# Supply_GEM.net
KiCad netlist of a schematic drawn in Altium Designer
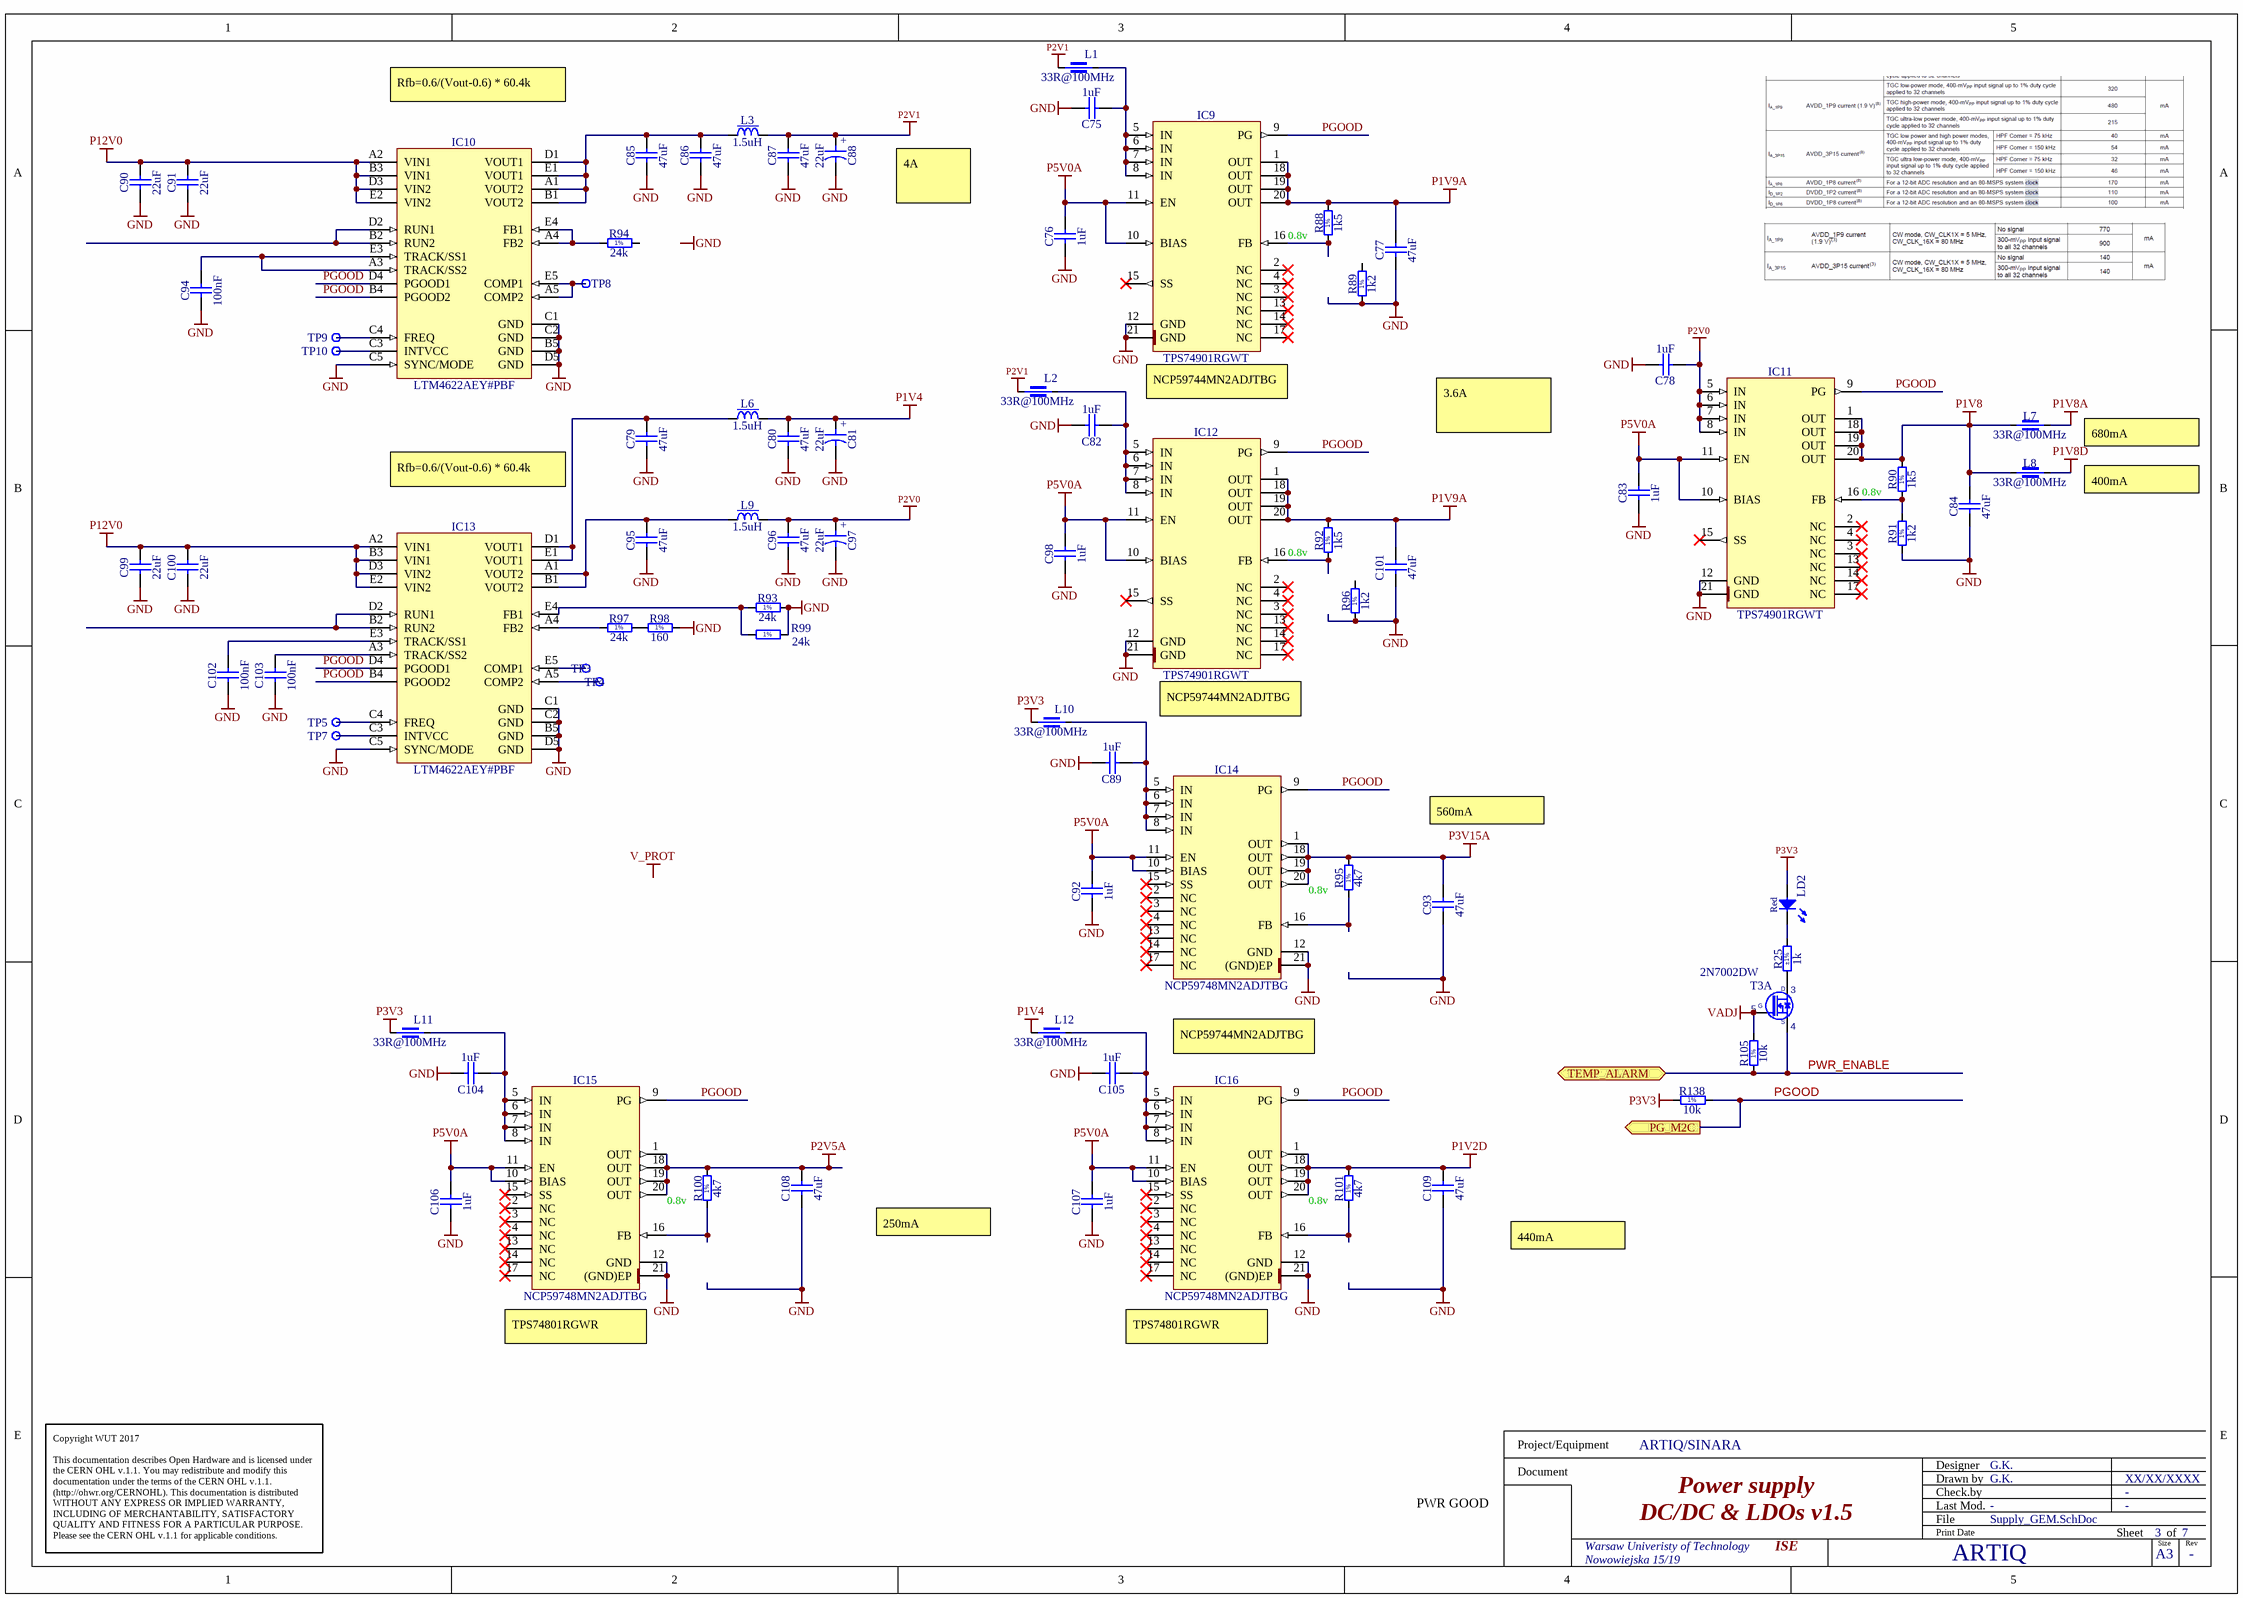
[diagram p0: Supply_GEM.SchDoc]

(export (version "E")
  (design (tool "Eeschema 10.0.6"))
  (components
    (comp (ref "C75")
      (value "1uF")
      (footprint "CAPC1005X55N")
      (description "Non-polarised capacitor")
      (fields (field (name "PART NUMBER") "CC0402_1UF_16V_10%_X5R") (field (name "VOLTAGE") "16V"))
      (libsource (lib "Capacitors") (part "Capacitor - non polarized"))
    )
    (comp (ref "C76")
      (value "1uF")
      (footprint "CAPC1005X55N")
      (description "Non-polarised capacitor")
      (fields (field (name "PART NUMBER") "CC0402_1UF_16V_10%_X5R") (field (name "VOLTAGE") "16V"))
      (libsource (lib "Capacitors") (part "Capacitor - non polarized"))
    )
    (comp (ref "C77")
      (value "47uF")
      (footprint "CAPC3225X270N")
      (description "Non-polarised capacitor")
      (fields (field (name "PART NUMBER") "CC1210_47UF_10V_20%_X5R") (field (name "VOLTAGE") "10V"))
      (libsource (lib "Capacitors") (part "Capacitor - non polarized"))
    )
    (comp (ref "C78")
      (value "1uF")
      (footprint "CAPC1005X55N")
      (description "Non-polarised capacitor")
      (fields (field (name "PART NUMBER") "CC0402_1UF_16V_10%_X5R") (field (name "VOLTAGE") "16V"))
      (libsource (lib "Capacitors") (part "Capacitor - non polarized"))
    )
    (comp (ref "C79")
      (value "47uF")
      (footprint "CAPC3225X270N")
      (description "Non-polarised capacitor")
      (fields (field (name "PART NUMBER") "CC1210_47UF_10V_20%_X5R") (field (name "VOLTAGE") "10V"))
      (libsource (lib "Capacitors") (part "Capacitor - non polarized"))
    )
    (comp (ref "C80")
      (value "47uF")
      (footprint "CAPC3225X270N")
      (description "Non-polarised capacitor")
      (fields (field (name "PART NUMBER") "CC1210_47UF_10V_20%_X5R") (field (name "VOLTAGE") "10V"))
      (libsource (lib "Capacitors") (part "Capacitor - non polarized"))
    )
    (comp (ref "C81")
      (value "22uF")
      (footprint "CAPMP3528X210N")
      (description "Polarised capacitor")
      (fields (field (name "PART NUMBER") "CTE3528-21_22UF_10V_10%_LESR0700") (field (name "VOLTAGE") "10V"))
      (libsource (lib "Capacitors") (part "Capacitor - polarized"))
    )
    (comp (ref "C82")
      (value "1uF")
      (footprint "CAPC1005X55N")
      (description "Non-polarised capacitor")
      (fields (field (name "PART NUMBER") "CC0402_1UF_16V_10%_X5R") (field (name "VOLTAGE") "16V"))
      (libsource (lib "Capacitors") (part "Capacitor - non polarized"))
    )
    (comp (ref "C83")
      (value "1uF")
      (footprint "CAPC1005X55N")
      (description "Non-polarised capacitor")
      (fields (field (name "PART NUMBER") "CC0402_1UF_16V_10%_X5R") (field (name "VOLTAGE") "16V"))
      (libsource (lib "Capacitors") (part "Capacitor - non polarized"))
    )
    (comp (ref "C84")
      (value "47uF")
      (footprint "CAPC3225X270N")
      (description "Non-polarised capacitor")
      (fields (field (name "PART NUMBER") "CC1210_47UF_10V_20%_X5R") (field (name "VOLTAGE") "10V"))
      (libsource (lib "Capacitors") (part "Capacitor - non polarized"))
    )
    (comp (ref "C85")
      (value "47uF")
      (footprint "CAPC3225X270N")
      (description "Non-polarised capacitor")
      (fields (field (name "PART NUMBER") "CC1210_47UF_10V_20%_X5R") (field (name "VOLTAGE") "10V"))
      (libsource (lib "Capacitors") (part "Capacitor - non polarized"))
    )
    (comp (ref "C86")
      (value "47uF")
      (footprint "CAPC3225X270N")
      (description "Non-polarised capacitor")
      (fields (field (name "PART NUMBER") "CC1210_47UF_10V_20%_X5R") (field (name "VOLTAGE") "10V"))
      (libsource (lib "Capacitors") (part "Capacitor - non polarized"))
    )
    (comp (ref "C87")
      (value "47uF")
      (footprint "CAPC3225X270N")
      (description "Non-polarised capacitor")
      (fields (field (name "PART NUMBER") "CC1210_47UF_10V_20%_X5R") (field (name "VOLTAGE") "10V"))
      (libsource (lib "Capacitors") (part "Capacitor - non polarized"))
    )
    (comp (ref "C88")
      (value "22uF")
      (footprint "CAPMP3528X210N")
      (description "Polarised capacitor")
      (fields (field (name "PART NUMBER") "CTE3528-21_22UF_10V_10%_LESR0700") (field (name "VOLTAGE") "10V"))
      (libsource (lib "Capacitors") (part "Capacitor - polarized"))
    )
    (comp (ref "C89")
      (value "1uF")
      (footprint "CAPC1005X55N")
      (description "Non-polarised capacitor")
      (fields (field (name "PART NUMBER") "CC0402_1UF_16V_10%_X5R") (field (name "VOLTAGE") "16V"))
      (libsource (lib "Capacitors") (part "Capacitor - non polarized"))
    )
    (comp (ref "C90")
      (value "22uF")
      (footprint "CAPC2012X135N")
      (description "Non-polarised capacitor")
      (fields (field (name "PART NUMBER") "CC0805_22UF_16V_10%_X5R") (field (name "VOLTAGE") "16V"))
      (libsource (lib "Capacitors") (part "Capacitor - non polarized"))
    )
    (comp (ref "C91")
      (value "22uF")
      (footprint "CAPC2012X135N")
      (description "Non-polarised capacitor")
      (fields (field (name "PART NUMBER") "CC0805_22UF_16V_10%_X5R") (field (name "VOLTAGE") "16V"))
      (libsource (lib "Capacitors") (part "Capacitor - non polarized"))
    )
    (comp (ref "C92")
      (value "1uF")
      (footprint "CAPC1005X55N")
      (description "Non-polarised capacitor")
      (fields (field (name "PART NUMBER") "CC0402_1UF_16V_10%_X5R") (field (name "VOLTAGE") "16V"))
      (libsource (lib "Capacitors") (part "Capacitor - non polarized"))
    )
    (comp (ref "C93")
      (value "47uF")
      (footprint "CAPC3225X270N")
      (description "Non-polarised capacitor")
      (fields (field (name "PART NUMBER") "CC1210_47UF_10V_20%_X5R") (field (name "VOLTAGE") "10V"))
      (libsource (lib "Capacitors") (part "Capacitor - non polarized"))
    )
    (comp (ref "C94")
      (value "100nF")
      (footprint "CAPC1005X55N")
      (description "Non-polarised capacitor")
      (fields (field (name "PART NUMBER") "CC0402_100NF_16V_10%_X5R") (field (name "VOLTAGE") "16V"))
      (libsource (lib "Capacitors") (part "Capacitor - non polarized"))
    )
    (comp (ref "C95")
      (value "47uF")
      (footprint "CAPC3225X270N")
      (description "Non-polarised capacitor")
      (fields (field (name "PART NUMBER") "CC1210_47UF_10V_20%_X5R") (field (name "VOLTAGE") "10V"))
      (libsource (lib "Capacitors") (part "Capacitor - non polarized"))
    )
    (comp (ref "C96")
      (value "47uF")
      (footprint "CAPC3225X270N")
      (description "Non-polarised capacitor")
      (fields (field (name "PART NUMBER") "CC1210_47UF_10V_20%_X5R") (field (name "VOLTAGE") "10V"))
      (libsource (lib "Capacitors") (part "Capacitor - non polarized"))
    )
    (comp (ref "C97")
      (value "22uF")
      (footprint "CAPMP3528X210N")
      (description "Polarised capacitor")
      (fields (field (name "PART NUMBER") "CTE3528-21_22UF_10V_10%_LESR0700") (field (name "VOLTAGE") "10V"))
      (libsource (lib "Capacitors") (part "Capacitor - polarized"))
    )
    (comp (ref "C98")
      (value "1uF")
      (footprint "CAPC1005X55N")
      (description "Non-polarised capacitor")
      (fields (field (name "PART NUMBER") "CC0402_1UF_16V_10%_X5R") (field (name "VOLTAGE") "16V"))
      (libsource (lib "Capacitors") (part "Capacitor - non polarized"))
    )
    (comp (ref "C99")
      (value "22uF")
      (footprint "CAPC2012X135N")
      (description "Non-polarised capacitor")
      (fields (field (name "PART NUMBER") "CC0805_22UF_16V_10%_X5R") (field (name "VOLTAGE") "16V"))
      (libsource (lib "Capacitors") (part "Capacitor - non polarized"))
    )
    (comp (ref "C100")
      (value "22uF")
      (footprint "CAPC2012X135N")
      (description "Non-polarised capacitor")
      (fields (field (name "PART NUMBER") "CC0805_22UF_16V_10%_X5R") (field (name "VOLTAGE") "16V"))
      (libsource (lib "Capacitors") (part "Capacitor - non polarized"))
    )
    (comp (ref "C101")
      (value "47uF")
      (footprint "CAPC3225X270N")
      (description "Non-polarised capacitor")
      (fields (field (name "PART NUMBER") "CC1210_47UF_10V_20%_X5R") (field (name "VOLTAGE") "10V"))
      (libsource (lib "Capacitors") (part "Capacitor - non polarized"))
    )
    (comp (ref "C102")
      (value "100nF")
      (footprint "CAPC1005X55N")
      (description "Non-polarised capacitor")
      (fields (field (name "PART NUMBER") "CC0402_100NF_16V_10%_X5R") (field (name "VOLTAGE") "16V"))
      (libsource (lib "Capacitors") (part "Capacitor - non polarized"))
    )
    (comp (ref "C103")
      (value "100nF")
      (footprint "CAPC1005X55N")
      (description "Non-polarised capacitor")
      (fields (field (name "PART NUMBER") "CC0402_100NF_16V_10%_X5R") (field (name "VOLTAGE") "16V"))
      (libsource (lib "Capacitors") (part "Capacitor - non polarized"))
    )
    (comp (ref "C104")
      (value "1uF")
      (footprint "CAPC1005X55N")
      (description "Non-polarised capacitor")
      (fields (field (name "PART NUMBER") "CC0402_1UF_16V_10%_X5R") (field (name "VOLTAGE") "16V"))
      (libsource (lib "Capacitors") (part "Capacitor - non polarized"))
    )
    (comp (ref "C105")
      (value "1uF")
      (footprint "CAPC1005X55N")
      (description "Non-polarised capacitor")
      (fields (field (name "PART NUMBER") "CC0402_1UF_16V_10%_X5R") (field (name "VOLTAGE") "16V"))
      (libsource (lib "Capacitors") (part "Capacitor - non polarized"))
    )
    (comp (ref "C106")
      (value "1uF")
      (footprint "CAPC1005X55N")
      (description "Non-polarised capacitor")
      (fields (field (name "PART NUMBER") "CC0402_1UF_16V_10%_X5R") (field (name "VOLTAGE") "16V"))
      (libsource (lib "Capacitors") (part "Capacitor - non polarized"))
    )
    (comp (ref "C107")
      (value "1uF")
      (footprint "CAPC1005X55N")
      (description "Non-polarised capacitor")
      (fields (field (name "PART NUMBER") "CC0402_1UF_16V_10%_X5R") (field (name "VOLTAGE") "16V"))
      (libsource (lib "Capacitors") (part "Capacitor - non polarized"))
    )
    (comp (ref "C108")
      (value "47uF")
      (footprint "CAPC3225X270N")
      (description "Non-polarised capacitor")
      (fields (field (name "PART NUMBER") "CC1210_47UF_10V_20%_X5R") (field (name "VOLTAGE") "10V"))
      (libsource (lib "Capacitors") (part "Capacitor - non polarized"))
    )
    (comp (ref "C109")
      (value "47uF")
      (footprint "CAPC3225X270N")
      (description "Non-polarised capacitor")
      (fields (field (name "PART NUMBER") "CC1210_47UF_10V_20%_X5R") (field (name "VOLTAGE") "10V"))
      (libsource (lib "Capacitors") (part "Capacitor - non polarized"))
    )
    (comp (ref "IC9")
      (value "TPS74901RGWT")
      (footprint "QFN65P500X500X100-21N-S325")
      (description "3A, 0.8 to 3.6V Adjustable Low-Dropout Linear Regulator with Programmable Soft-Start")
      (fields (field (name "MANUFACTURER") "TEXAS INSTRUMENTS"))
      (libsource (lib "ICs And Semiconductors") (part "TPS74901RGWT"))
    )
    (comp (ref "IC10")
      (value "LTM4622AEY#PBF")
      (footprint "BGA25C127P5X5_625X625X262")
      (description "3.6V-20V To 1.5V-12V, Dual 2A or Single 4A  Ultrathin Step-Down DC/DC µModule Regulator")
      (fields (field (name "MANUFACTURER") "LINEAR TECHNOLOGY"))
      (libsource (lib "ICs And Semiconductors") (part "LTM4622A"))
    )
    (comp (ref "IC11")
      (value "TPS74901RGWT")
      (footprint "QFN65P500X500X100-21N-S325")
      (description "3A, 0.8 to 3.6V Adjustable Low-Dropout Linear Regulator with Programmable Soft-Start")
      (fields (field (name "MANUFACTURER") "TEXAS INSTRUMENTS"))
      (libsource (lib "ICs And Semiconductors") (part "TPS74901RGWT"))
    )
    (comp (ref "IC12")
      (value "TPS74901RGWT")
      (footprint "QFN65P500X500X100-21N-S325")
      (description "3A, 0.8 to 3.6V Adjustable Low-Dropout Linear Regulator with Programmable Soft-Start")
      (fields (field (name "MANUFACTURER") "TEXAS INSTRUMENTS"))
      (libsource (lib "ICs And Semiconductors") (part "TPS74901RGWT"))
    )
    (comp (ref "IC13")
      (value "LTM4622AEY#PBF")
      (footprint "BGA25C127P5X5_625X625X262")
      (description "3.6V-20V To 1.5V-12V, Dual 2A or Single 4A  Ultrathin Step-Down DC/DC µModule Regulator")
      (fields (field (name "MANUFACTURER") "LINEAR TECHNOLOGY"))
      (libsource (lib "ICs And Semiconductors") (part "LTM4622A"))
    )
    (comp (ref "IC14")
      (value "NCP59748MN2ADJTBG")
      (footprint "QFN65P500X500X100-21N-S325")
      (description "1.5A, Dual-Rail Very Low‐Dropout Linear Regulator with Programmable Soft‐Start")
      (fields (field (name "MANUFACTURER") "ON SEMICONDUCTOR"))
      (libsource (lib "ICs And Semiconductors") (part "NCP59748MN2ADJTBG"))
    )
    (comp (ref "IC15")
      (value "NCP59748MN2ADJTBG")
      (footprint "QFN65P500X500X100-21N-S325")
      (description "1.5A, Dual-Rail Very Low‐Dropout Linear Regulator with Programmable Soft‐Start")
      (fields (field (name "MANUFACTURER") "ON SEMICONDUCTOR"))
      (libsource (lib "ICs And Semiconductors") (part "NCP59748MN2ADJTBG"))
    )
    (comp (ref "IC16")
      (value "NCP59748MN2ADJTBG")
      (footprint "QFN65P500X500X100-21N-S325")
      (description "1.5A, Dual-Rail Very Low‐Dropout Linear Regulator with Programmable Soft‐Start")
      (fields (field (name "MANUFACTURER") "ON SEMICONDUCTOR"))
      (libsource (lib "ICs And Semiconductors") (part "NCP59748MN2ADJTBG"))
    )
    (comp (ref "L1")
      (value "33R@100MHz")
      (footprint "INDC1608X95N")
      (fields
        (field (name "PART NUMBER") "IND0603_MURATA_BLM18PG330SN1D")
        (field (name "POWER") "3A")
        (field (name "TOLERANCE") "±25%")
      )
      (libsource (lib "Inductors & Transformers") (part "Ferrite Bead"))
    )
    (comp (ref "L2")
      (value "33R@100MHz")
      (footprint "INDC1608X95N")
      (fields
        (field (name "PART NUMBER") "IND0603_MURATA_BLM18PG330SN1D")
        (field (name "POWER") "3A")
        (field (name "TOLERANCE") "±25%")
      )
      (libsource (lib "Inductors & Transformers") (part "Ferrite Bead"))
    )
    (comp (ref "L3")
      (value "1.5uH")
      (footprint "IND_TDK_SPM6530")
      (description "Inductor With Core")
      (fields (field (name "PART NUMBER") "IND_1.5UH_20%_TDK_SPM6530") (field (name "POWER") "11A"))
      (libsource (lib "Inductors & Transformers") (part "Inductor With Magnetic core"))
    )
    (comp (ref "L6")
      (value "1.5uH")
      (footprint "IND_TDK_SPM6530")
      (description "Inductor With Core")
      (fields (field (name "PART NUMBER") "IND_1.5UH_20%_TDK_SPM6530") (field (name "POWER") "11A"))
      (libsource (lib "Inductors & Transformers") (part "Inductor With Magnetic core"))
    )
    (comp (ref "L7")
      (value "33R@100MHz")
      (footprint "INDC1608X95N")
      (fields
        (field (name "PART NUMBER") "IND0603_MURATA_BLM18PG330SN1D")
        (field (name "POWER") "3A")
        (field (name "TOLERANCE") "±25%")
      )
      (libsource (lib "Inductors & Transformers") (part "Ferrite Bead"))
    )
    (comp (ref "L8")
      (value "33R@100MHz")
      (footprint "INDC1608X95N")
      (fields
        (field (name "PART NUMBER") "IND0603_MURATA_BLM18PG330SN1D")
        (field (name "POWER") "3A")
        (field (name "TOLERANCE") "±25%")
      )
      (libsource (lib "Inductors & Transformers") (part "Ferrite Bead"))
    )
    (comp (ref "L9")
      (value "1.5uH")
      (footprint "IND_TDK_SPM6530")
      (description "Inductor With Core")
      (fields (field (name "PART NUMBER") "IND_1.5UH_20%_TDK_SPM6530") (field (name "POWER") "11A"))
      (libsource (lib "Inductors & Transformers") (part "Inductor With Magnetic core"))
    )
    (comp (ref "L10")
      (value "33R@100MHz")
      (footprint "INDC1608X95N")
      (fields
        (field (name "PART NUMBER") "IND0603_MURATA_BLM18PG330SN1D")
        (field (name "POWER") "3A")
        (field (name "TOLERANCE") "±25%")
      )
      (libsource (lib "Inductors & Transformers") (part "Ferrite Bead"))
    )
    (comp (ref "L11")
      (value "33R@100MHz")
      (footprint "INDC1608X95N")
      (fields
        (field (name "PART NUMBER") "IND0603_MURATA_BLM18PG330SN1D")
        (field (name "POWER") "3A")
        (field (name "TOLERANCE") "±25%")
      )
      (libsource (lib "Inductors & Transformers") (part "Ferrite Bead"))
    )
    (comp (ref "L12")
      (value "33R@100MHz")
      (footprint "INDC1608X95N")
      (fields
        (field (name "PART NUMBER") "IND0603_MURATA_BLM18PG330SN1D")
        (field (name "POWER") "3A")
        (field (name "TOLERANCE") "±25%")
      )
      (libsource (lib "Inductors & Transformers") (part "Ferrite Bead"))
    )
    (comp (ref "LD2")
      (value "Red")
      (footprint "LED_AVAGO_HSMC-C110")
      (description "LED Red 1C 2A")
      (fields
        (field (name "PART NUMBER") "LED_AVAGO_HSMC-C110")
        (field (name "MANUFACTURER") "AVAGO TECHNOLOGIES")
      )
      (libsource (lib "ICs And Semiconductors") (part "LED Red 1C 2A"))
    )
    (comp (ref "R25")
      (value "1k")
      (footprint "RESC1005X40N")
      (description "Resistor - 1%")
      (fields
        (field (name "TOLERANCE") "±1%")
        (field (name "PART NUMBER") "R0402_1K_1%_0.0625W_100PPM")
        (field (name "POWER") "0.0625W")
      )
      (libsource (lib "") (part "Resistor - 1%_1"))
    )
    (comp (ref "R88")
      (value "1k5")
      (footprint "RESC1608X55N")
      (description "Resistor - 1%")
      (fields (field (name "PART NUMBER") "R0603_1K5_1%_0.1W_100PPM") (field (name "POWER") "0.1W"))
      (libsource (lib "Resistors") (part "Resistor - 1%"))
    )
    (comp (ref "R89")
      (value "1k2")
      (footprint "RESC1608X55N")
      (description "Resistor - 1%")
      (fields (field (name "PART NUMBER") "R0603_1K2_1%_0.1W_100PPM") (field (name "POWER") "0.1W"))
      (libsource (lib "Resistors") (part "Resistor - 1%"))
    )
    (comp (ref "R90")
      (value "1k5")
      (footprint "RESC1608X55N")
      (description "Resistor - 1%")
      (fields (field (name "PART NUMBER") "R0603_1K5_1%_0.1W_100PPM") (field (name "POWER") "0.1W"))
      (libsource (lib "Resistors") (part "Resistor - 1%"))
    )
    (comp (ref "R91")
      (value "1k2")
      (footprint "RESC1608X55N")
      (description "Resistor - 1%")
      (fields (field (name "PART NUMBER") "R0603_1K2_1%_0.1W_100PPM") (field (name "POWER") "0.1W"))
      (libsource (lib "Resistors") (part "Resistor - 1%"))
    )
    (comp (ref "R92")
      (value "1k5")
      (footprint "RESC1608X55N")
      (description "Resistor - 1%")
      (fields (field (name "PART NUMBER") "R0603_1K5_1%_0.1W_100PPM") (field (name "POWER") "0.1W"))
      (libsource (lib "Resistors") (part "Resistor - 1%"))
    )
    (comp (ref "R93")
      (value "24k")
      (footprint "RESC1608X55N")
      (description "Resistor - 1%")
      (fields (field (name "PART NUMBER") "R0603_24K_1%_0.1W_100PPM") (field (name "POWER") "0.1W"))
      (libsource (lib "Resistors") (part "Resistor - 1%"))
    )
    (comp (ref "R94")
      (value "24k")
      (footprint "RESC1608X55N")
      (description "Resistor - 1%")
      (fields (field (name "PART NUMBER") "R0603_24K_1%_0.1W_100PPM") (field (name "POWER") "0.1W"))
      (libsource (lib "Resistors") (part "Resistor - 1%"))
    )
    (comp (ref "R95")
      (value "4k7")
      (footprint "RESC1608X55N")
      (description "Resistor - 1%")
      (fields (field (name "PART NUMBER") "R0603_4K7_1%_0.1W_100PPM") (field (name "POWER") "0.1W"))
      (libsource (lib "Resistors") (part "Resistor - 1%"))
    )
    (comp (ref "R96")
      (value "1k2")
      (footprint "RESC1608X55N")
      (description "Resistor - 1%")
      (fields (field (name "PART NUMBER") "R0603_1K2_1%_0.1W_100PPM") (field (name "POWER") "0.1W"))
      (libsource (lib "Resistors") (part "Resistor - 1%"))
    )
    (comp (ref "R97")
      (value "24k")
      (footprint "RESC1608X55N")
      (description "Resistor - 1%")
      (fields (field (name "PART NUMBER") "R0603_24K_1%_0.1W_100PPM") (field (name "POWER") "0.1W"))
      (libsource (lib "Resistors") (part "Resistor - 1%"))
    )
    (comp (ref "R98")
      (value "160")
      (footprint "RESC1608X55N")
      (description "Resistor - 1%")
      (fields (field (name "PART NUMBER") "R0603_160R_1%_0.1W_100PPM") (field (name "POWER") "0.1W"))
      (libsource (lib "Resistors") (part "Resistor - 1%"))
    )
    (comp (ref "R99")
      (value "24k")
      (footprint "RESC1608X55N")
      (description "Resistor - 1%")
      (fields (field (name "PART NUMBER") "R0603_24K_1%_0.1W_100PPM") (field (name "POWER") "0.1W"))
      (libsource (lib "Resistors") (part "Resistor - 1%"))
    )
    (comp (ref "R100")
      (value "4k7")
      (footprint "RESC1608X55N")
      (description "Resistor - 1%")
      (fields (field (name "PART NUMBER") "R0603_4K7_1%_0.1W_100PPM") (field (name "POWER") "0.1W"))
      (libsource (lib "Resistors") (part "Resistor - 1%"))
    )
    (comp (ref "R101")
      (value "4k7")
      (footprint "RESC1608X55N")
      (description "Resistor - 1%")
      (fields (field (name "PART NUMBER") "R0603_4K7_1%_0.1W_100PPM") (field (name "POWER") "0.1W"))
      (libsource (lib "Resistors") (part "Resistor - 1%"))
    )
    (comp (ref "R105")
      (value "10k")
      (footprint "RESC1005X40N")
      (description "Resistor - 1%")
      (fields (field (name "PART NUMBER") "R0402_10K_1%_0.0625W_100PPM") (field (name "POWER") "0.0625W"))
      (libsource (lib "Resistors") (part "Resistor - 1%"))
    )
    (comp (ref "R138")
      (value "10k")
      (footprint "RESC1005X40N")
      (description "Resistor - 1%")
      (fields (field (name "PART NUMBER") "R0402_10K_1%_0.0625W_100PPM") (field (name "POWER") "0.0625W"))
      (libsource (lib "Resistors") (part "Resistor - 1%"))
    )
    (comp (ref "T3")
      (value "2N7002DW")
      (footprint "SOT65P210X110-6N")
      (description "60 V, 115 mA, Dual N-Channel Field Effect Transistor, Enhancement Mode")
      (fields (field (name "MANUFACTURER") "ON SEMICONDUCTOR"))
      (libsource (lib "ICs And Semiconductors") (part "2N7002DW"))
    )
    (comp (ref "TP3")
      (value "Test Point")
      (footprint "TPS127")
      (fields (field (name "PART NUMBER") "SMD_PAD_1.27X1.27MM"))
      (libsource (lib "Eletro-mechanical") (part "Test Point"))
    )
    (comp (ref "TP4")
      (value "Test Point")
      (footprint "TPS127")
      (fields (field (name "PART NUMBER") "SMD_PAD_1.27X1.27MM"))
      (libsource (lib "Eletro-mechanical") (part "Test Point"))
    )
    (comp (ref "TP5")
      (value "Test Point")
      (footprint "TPS127")
      (fields (field (name "PART NUMBER") "SMD_PAD_1.27X1.27MM"))
      (libsource (lib "Eletro-mechanical") (part "Test Point"))
    )
    (comp (ref "TP7")
      (value "Test Point")
      (footprint "TPS127")
      (fields (field (name "PART NUMBER") "SMD_PAD_1.27X1.27MM"))
      (libsource (lib "Eletro-mechanical") (part "Test Point"))
    )
    (comp (ref "TP8")
      (value "Test Point")
      (footprint "TPS127")
      (fields (field (name "PART NUMBER") "SMD_PAD_1.27X1.27MM"))
      (libsource (lib "Eletro-mechanical") (part "Test Point"))
    )
    (comp (ref "TP9")
      (value "Test Point")
      (footprint "TPS127")
      (fields (field (name "PART NUMBER") "SMD_PAD_1.27X1.27MM"))
      (libsource (lib "Eletro-mechanical") (part "Test Point"))
    )
    (comp (ref "TP10")
      (value "Test Point")
      (footprint "TPS127")
      (fields (field (name "PART NUMBER") "SMD_PAD_1.27X1.27MM"))
      (libsource (lib "Eletro-mechanical") (part "Test Point"))
    )
  )
  (nets
    (net (code "1") (name "/PGOOD") (class "Default")
      (node (ref "IC10") (pin "B4") (pinfunction "PGOOD2_B4") (pintype "open_collector"))
      (node (ref "IC10") (pin "D4") (pinfunction "PGOOD1_D4") (pintype "open_collector"))
      (node (ref "IC11") (pin "9") (pinfunction "PG_9") (pintype "output"))
      (node (ref "IC12") (pin "9") (pinfunction "PG_9") (pintype "output"))
      (node (ref "IC13") (pin "B4") (pinfunction "PGOOD2_B4") (pintype "open_collector"))
      (node (ref "IC13") (pin "D4") (pinfunction "PGOOD1_D4") (pintype "open_collector"))
      (node (ref "IC14") (pin "9") (pinfunction "PG_9") (pintype "output"))
      (node (ref "IC15") (pin "9") (pinfunction "PG_9") (pintype "output"))
      (node (ref "IC16") (pin "9") (pinfunction "PG_9") (pintype "output"))
      (node (ref "IC9") (pin "9") (pinfunction "PG_9") (pintype "output"))
      (node (ref "R138") (pin "2") (pinfunction "2_2") (pintype "passive"))
    )
    (net (code "2") (name "/PWR_ENABLE") (class "Default")
      (node (ref "R105") (pin "1") (pinfunction "1_1") (pintype "passive"))
      (node (ref "T3") (pin "4") (pinfunction "S1_4") (pintype "passive"))
    )
    (net (code "3") (name "GND") (class "Default")
      (node (ref "C100") (pin "1") (pinfunction "1_1") (pintype "passive"))
      (node (ref "C101") (pin "1") (pinfunction "1_1") (pintype "passive"))
      (node (ref "C102") (pin "1") (pinfunction "1_1") (pintype "passive"))
      (node (ref "C103") (pin "1") (pinfunction "1_1") (pintype "passive"))
      (node (ref "C104") (pin "2") (pinfunction "2_2") (pintype "passive"))
      (node (ref "C105") (pin "2") (pinfunction "2_2") (pintype "passive"))
      (node (ref "C106") (pin "1") (pinfunction "1_1") (pintype "passive"))
      (node (ref "C107") (pin "1") (pinfunction "1_1") (pintype "passive"))
      (node (ref "C108") (pin "1") (pinfunction "1_1") (pintype "passive"))
      (node (ref "C109") (pin "1") (pinfunction "1_1") (pintype "passive"))
      (node (ref "C75") (pin "2") (pinfunction "2_2") (pintype "passive"))
      (node (ref "C76") (pin "1") (pinfunction "1_1") (pintype "passive"))
      (node (ref "C77") (pin "1") (pinfunction "1_1") (pintype "passive"))
      (node (ref "C78") (pin "2") (pinfunction "2_2") (pintype "passive"))
      (node (ref "C79") (pin "1") (pinfunction "1_1") (pintype "passive"))
      (node (ref "C80") (pin "1") (pinfunction "1_1") (pintype "passive"))
      (node (ref "C81") (pin "2") (pinfunction "2_2") (pintype "passive"))
      (node (ref "C82") (pin "2") (pinfunction "2_2") (pintype "passive"))
      (node (ref "C83") (pin "1") (pinfunction "1_1") (pintype "passive"))
      (node (ref "C84") (pin "1") (pinfunction "1_1") (pintype "passive"))
      (node (ref "C85") (pin "1") (pinfunction "1_1") (pintype "passive"))
      (node (ref "C86") (pin "1") (pinfunction "1_1") (pintype "passive"))
      (node (ref "C87") (pin "1") (pinfunction "1_1") (pintype "passive"))
      (node (ref "C88") (pin "2") (pinfunction "2_2") (pintype "passive"))
      (node (ref "C89") (pin "2") (pinfunction "2_2") (pintype "passive"))
      (node (ref "C90") (pin "1") (pinfunction "1_1") (pintype "passive"))
      (node (ref "C91") (pin "1") (pinfunction "1_1") (pintype "passive"))
      (node (ref "C92") (pin "1") (pinfunction "1_1") (pintype "passive"))
      (node (ref "C93") (pin "1") (pinfunction "1_1") (pintype "passive"))
      (node (ref "C94") (pin "1") (pinfunction "1_1") (pintype "passive"))
      (node (ref "C95") (pin "1") (pinfunction "1_1") (pintype "passive"))
      (node (ref "C96") (pin "1") (pinfunction "1_1") (pintype "passive"))
      (node (ref "C97") (pin "2") (pinfunction "2_2") (pintype "passive"))
      (node (ref "C98") (pin "1") (pinfunction "1_1") (pintype "passive"))
      (node (ref "C99") (pin "1") (pinfunction "1_1") (pintype "passive"))
      (node (ref "IC10") (pin "B5") (pinfunction "GND_B5") (pintype "power_in"))
      (node (ref "IC10") (pin "C1") (pinfunction "GND_C1") (pintype "power_in"))
      (node (ref "IC10") (pin "C2") (pinfunction "GND_C2") (pintype "power_in"))
      (node (ref "IC10") (pin "C5") (pinfunction "SYNC/MODE_C5") (pintype "input"))
      (node (ref "IC10") (pin "D5") (pinfunction "GND_D5") (pintype "power_in"))
      (node (ref "IC11") (pin "12") (pinfunction "GND_12") (pintype "power_in"))
      (node (ref "IC11") (pin "21") (pinfunction "GND_21") (pintype "power_in"))
      (node (ref "IC12") (pin "12") (pinfunction "GND_12") (pintype "power_in"))
      (node (ref "IC12") (pin "21") (pinfunction "GND_21") (pintype "power_in"))
      (node (ref "IC13") (pin "B5") (pinfunction "GND_B5") (pintype "power_in"))
      (node (ref "IC13") (pin "C1") (pinfunction "GND_C1") (pintype "power_in"))
      (node (ref "IC13") (pin "C2") (pinfunction "GND_C2") (pintype "power_in"))
      (node (ref "IC13") (pin "C5") (pinfunction "SYNC/MODE_C5") (pintype "input"))
      (node (ref "IC13") (pin "D5") (pinfunction "GND_D5") (pintype "power_in"))
      (node (ref "IC14") (pin "12") (pinfunction "GND_12") (pintype "power_in"))
      (node (ref "IC14") (pin "21") (pinfunction "(GND)EP_21") (pintype "power_in"))
      (node (ref "IC15") (pin "12") (pinfunction "GND_12") (pintype "power_in"))
      (node (ref "IC15") (pin "21") (pinfunction "(GND)EP_21") (pintype "power_in"))
      (node (ref "IC16") (pin "12") (pinfunction "GND_12") (pintype "power_in"))
      (node (ref "IC16") (pin "21") (pinfunction "(GND)EP_21") (pintype "power_in"))
      (node (ref "IC9") (pin "12") (pinfunction "GND_12") (pintype "power_in"))
      (node (ref "IC9") (pin "21") (pinfunction "GND_21") (pintype "power_in"))
      (node (ref "R89") (pin "1") (pinfunction "1_1") (pintype "passive"))
      (node (ref "R91") (pin "1") (pinfunction "1_1") (pintype "passive"))
      (node (ref "R93") (pin "2") (pinfunction "2_2") (pintype "passive"))
      (node (ref "R96") (pin "1") (pinfunction "1_1") (pintype "passive"))
      (node (ref "R98") (pin "2") (pinfunction "2_2") (pintype "passive"))
      (node (ref "R99") (pin "2") (pinfunction "2_2") (pintype "passive"))
    )
    (net (code "4") (name "Net-(C75-Pad1)") (class "Default")
      (node (ref "C75") (pin "1") (pinfunction "1_1") (pintype "passive"))
      (node (ref "IC9") (pin "5") (pinfunction "IN_5") (pintype "input"))
      (node (ref "IC9") (pin "6") (pinfunction "IN_6") (pintype "input"))
      (node (ref "IC9") (pin "7") (pinfunction "IN_7") (pintype "input"))
      (node (ref "IC9") (pin "8") (pinfunction "IN_8") (pintype "input"))
      (node (ref "L1") (pin "2") (pinfunction "2_2") (pintype "passive"))
    )
    (net (code "5") (name "Net-(C79-Pad2)") (class "Default")
      (node (ref "C79") (pin "2") (pinfunction "2_2") (pintype "passive"))
      (node (ref "IC13") (pin "D1") (pinfunction "VOUT1_D1") (pintype "power_in"))
      (node (ref "IC13") (pin "E1") (pinfunction "VOUT1_E1") (pintype "power_in"))
      (node (ref "L6") (pin "1") (pinfunction "1_1") (pintype "passive"))
    )
    (net (code "6") (name "Net-(C82-Pad1)") (class "Default")
      (node (ref "C82") (pin "1") (pinfunction "1_1") (pintype "passive"))
      (node (ref "IC12") (pin "5") (pinfunction "IN_5") (pintype "input"))
      (node (ref "IC12") (pin "6") (pinfunction "IN_6") (pintype "input"))
      (node (ref "IC12") (pin "7") (pinfunction "IN_7") (pintype "input"))
      (node (ref "IC12") (pin "8") (pinfunction "IN_8") (pintype "input"))
      (node (ref "L2") (pin "2") (pinfunction "2_2") (pintype "passive"))
    )
    (net (code "7") (name "Net-(C85-Pad2)") (class "Default")
      (node (ref "C85") (pin "2") (pinfunction "2_2") (pintype "passive"))
      (node (ref "C86") (pin "2") (pinfunction "2_2") (pintype "passive"))
      (node (ref "IC10") (pin "A1") (pinfunction "VOUT2_A1") (pintype "power_in"))
      (node (ref "IC10") (pin "B1") (pinfunction "VOUT2_B1") (pintype "power_in"))
      (node (ref "IC10") (pin "D1") (pinfunction "VOUT1_D1") (pintype "power_in"))
      (node (ref "IC10") (pin "E1") (pinfunction "VOUT1_E1") (pintype "power_in"))
      (node (ref "L3") (pin "1") (pinfunction "1_1") (pintype "passive"))
    )
    (net (code "8") (name "Net-(C89-Pad1)") (class "Default")
      (node (ref "C89") (pin "1") (pinfunction "1_1") (pintype "passive"))
      (node (ref "IC14") (pin "5") (pinfunction "IN_5") (pintype "input"))
      (node (ref "IC14") (pin "6") (pinfunction "IN_6") (pintype "input"))
      (node (ref "IC14") (pin "7") (pinfunction "IN_7") (pintype "input"))
      (node (ref "IC14") (pin "8") (pinfunction "IN_8") (pintype "input"))
      (node (ref "L10") (pin "2") (pinfunction "2_2") (pintype "passive"))
    )
    (net (code "9") (name "Net-(C95-Pad2)") (class "Default")
      (node (ref "C95") (pin "2") (pinfunction "2_2") (pintype "passive"))
      (node (ref "IC13") (pin "A1") (pinfunction "VOUT2_A1") (pintype "power_in"))
      (node (ref "IC13") (pin "B1") (pinfunction "VOUT2_B1") (pintype "power_in"))
      (node (ref "L9") (pin "1") (pinfunction "1_1") (pintype "passive"))
    )
    (net (code "10") (name "Net-(C104-Pad1)") (class "Default")
      (node (ref "C104") (pin "1") (pinfunction "1_1") (pintype "passive"))
      (node (ref "IC15") (pin "5") (pinfunction "IN_5") (pintype "input"))
      (node (ref "IC15") (pin "6") (pinfunction "IN_6") (pintype "input"))
      (node (ref "IC15") (pin "7") (pinfunction "IN_7") (pintype "input"))
      (node (ref "IC15") (pin "8") (pinfunction "IN_8") (pintype "input"))
      (node (ref "L11") (pin "2") (pinfunction "2_2") (pintype "passive"))
    )
    (net (code "11") (name "Net-(C105-Pad1)") (class "Default")
      (node (ref "C105") (pin "1") (pinfunction "1_1") (pintype "passive"))
      (node (ref "IC16") (pin "5") (pinfunction "IN_5") (pintype "input"))
      (node (ref "IC16") (pin "6") (pinfunction "IN_6") (pintype "input"))
      (node (ref "IC16") (pin "7") (pinfunction "IN_7") (pintype "input"))
      (node (ref "IC16") (pin "8") (pinfunction "IN_8") (pintype "input"))
      (node (ref "L12") (pin "2") (pinfunction "2_2") (pintype "passive"))
    )
    (net (code "12") (name "Net-(IC9-FB)") (class "Default")
      (node (ref "IC9") (pin "16") (pinfunction "FB_16") (pintype "input"))
      (node (ref "R88") (pin "1") (pinfunction "1_1") (pintype "passive"))
    )
    (net (code "13") (name "Net-(IC10-COMP1)") (class "Default")
      (node (ref "IC10") (pin "A5") (pinfunction "COMP2_A5") (pintype "input"))
      (node (ref "IC10") (pin "E5") (pinfunction "COMP1_E5") (pintype "input"))
      (node (ref "TP8") (pin "1") (pinfunction "1_1") (pintype "bidirectional"))
    )
    (net (code "14") (name "Net-(IC10-FB1)") (class "Default")
      (node (ref "IC10") (pin "A4") (pinfunction "FB2_A4") (pintype "input"))
      (node (ref "IC10") (pin "E4") (pinfunction "FB1_E4") (pintype "input"))
      (node (ref "R94") (pin "1") (pinfunction "1_1") (pintype "passive"))
    )
    (net (code "15") (name "Net-(IC10-FREQ)") (class "Default")
      (node (ref "IC10") (pin "C4") (pinfunction "FREQ_C4") (pintype "input"))
      (node (ref "TP9") (pin "1") (pinfunction "1_1") (pintype "bidirectional"))
    )
    (net (code "16") (name "Net-(IC10-INTVCC)") (class "Default")
      (node (ref "IC10") (pin "C3") (pinfunction "INTVCC_C3") (pintype "power_in"))
      (node (ref "TP10") (pin "1") (pinfunction "1_1") (pintype "bidirectional"))
    )
    (net (code "17") (name "Net-(IC10-RUN1)") (class "Default")
      (node (ref "IC10") (pin "B2") (pinfunction "RUN2_B2") (pintype "input"))
      (node (ref "IC10") (pin "D2") (pinfunction "RUN1_D2") (pintype "input"))
    )
    (net (code "18") (name "Net-(IC10-TRACK{slash}SS1)") (class "Default")
      (node (ref "C94") (pin "2") (pinfunction "2_2") (pintype "passive"))
      (node (ref "IC10") (pin "A3") (pinfunction "TRACK/SS2_A3") (pintype "input"))
      (node (ref "IC10") (pin "E3") (pinfunction "TRACK/SS1_E3") (pintype "input"))
    )
    (net (code "19") (name "Net-(IC11-FB)") (class "Default")
      (node (ref "IC11") (pin "16") (pinfunction "FB_16") (pintype "input"))
      (node (ref "R90") (pin "1") (pinfunction "1_1") (pintype "passive"))
      (node (ref "R91") (pin "2") (pinfunction "2_2") (pintype "passive"))
    )
    (net (code "20") (name "Net-(IC12-FB)") (class "Default")
      (node (ref "IC12") (pin "16") (pinfunction "FB_16") (pintype "input"))
      (node (ref "R92") (pin "1") (pinfunction "1_1") (pintype "passive"))
    )
    (net (code "21") (name "Net-(IC13-COMP1)") (class "Default")
      (node (ref "IC13") (pin "E5") (pinfunction "COMP1_E5") (pintype "input"))
      (node (ref "TP3") (pin "1") (pinfunction "1_1") (pintype "bidirectional"))
    )
    (net (code "22") (name "Net-(IC13-COMP2)") (class "Default")
      (node (ref "IC13") (pin "A5") (pinfunction "COMP2_A5") (pintype "input"))
      (node (ref "TP4") (pin "1") (pinfunction "1_1") (pintype "bidirectional"))
    )
    (net (code "23") (name "Net-(IC13-FB1)") (class "Default")
      (node (ref "IC13") (pin "E4") (pinfunction "FB1_E4") (pintype "input"))
      (node (ref "R93") (pin "1") (pinfunction "1_1") (pintype "passive"))
      (node (ref "R99") (pin "1") (pinfunction "1_1") (pintype "passive"))
    )
    (net (code "24") (name "Net-(IC13-FB2)") (class "Default")
      (node (ref "IC13") (pin "A4") (pinfunction "FB2_A4") (pintype "input"))
      (node (ref "R97") (pin "1") (pinfunction "1_1") (pintype "passive"))
    )
    (net (code "25") (name "Net-(IC13-FREQ)") (class "Default")
      (node (ref "IC13") (pin "C4") (pinfunction "FREQ_C4") (pintype "input"))
      (node (ref "TP5") (pin "1") (pinfunction "1_1") (pintype "bidirectional"))
    )
    (net (code "26") (name "Net-(IC13-INTVCC)") (class "Default")
      (node (ref "IC13") (pin "C3") (pinfunction "INTVCC_C3") (pintype "power_in"))
      (node (ref "TP7") (pin "1") (pinfunction "1_1") (pintype "bidirectional"))
    )
    (net (code "27") (name "Net-(IC13-RUN1)") (class "Default")
      (node (ref "IC13") (pin "B2") (pinfunction "RUN2_B2") (pintype "input"))
      (node (ref "IC13") (pin "D2") (pinfunction "RUN1_D2") (pintype "input"))
    )
    (net (code "28") (name "Net-(IC13-TRACK{slash}SS1)") (class "Default")
      (node (ref "C102") (pin "2") (pinfunction "2_2") (pintype "passive"))
      (node (ref "IC13") (pin "E3") (pinfunction "TRACK/SS1_E3") (pintype "input"))
    )
    (net (code "29") (name "Net-(IC13-TRACK{slash}SS2)") (class "Default")
      (node (ref "C103") (pin "2") (pinfunction "2_2") (pintype "passive"))
      (node (ref "IC13") (pin "A3") (pinfunction "TRACK/SS2_A3") (pintype "input"))
    )
    (net (code "30") (name "Net-(IC14-FB)") (class "Default")
      (node (ref "IC14") (pin "16") (pinfunction "FB_16") (pintype "input"))
      (node (ref "R95") (pin "1") (pinfunction "1_1") (pintype "passive"))
    )
    (net (code "31") (name "Net-(IC15-FB)") (class "Default")
      (node (ref "IC15") (pin "16") (pinfunction "FB_16") (pintype "input"))
      (node (ref "R100") (pin "1") (pinfunction "1_1") (pintype "passive"))
    )
    (net (code "32") (name "Net-(IC16-FB)") (class "Default")
      (node (ref "IC16") (pin "16") (pinfunction "FB_16") (pintype "input"))
      (node (ref "R101") (pin "1") (pinfunction "1_1") (pintype "passive"))
    )
    (net (code "33") (name "Net-(LD2-C)") (class "Default")
      (node (ref "LD2") (pin "1") (pinfunction "C_1") (pintype "passive"))
      (node (ref "R25") (pin "2") (pinfunction "2_2") (pintype "passive"))
    )
    (net (code "34") (name "Net-(R97-Pad2)") (class "Default")
      (node (ref "R97") (pin "2") (pinfunction "2_2") (pintype "passive"))
      (node (ref "R98") (pin "1") (pinfunction "1_1") (pintype "passive"))
    )
    (net (code "35") (name "Net-(T3A-D1)") (class "Default")
      (node (ref "R25") (pin "1") (pinfunction "1_1") (pintype "passive"))
      (node (ref "T3") (pin "3") (pinfunction "D1_3") (pintype "passive"))
    )
    (net (code "36") (name "P1V2D") (class "Default")
      (node (ref "C109") (pin "2") (pinfunction "2_2") (pintype "passive"))
      (node (ref "IC16") (pin "1") (pinfunction "OUT_1") (pintype "output"))
      (node (ref "IC16") (pin "18") (pinfunction "OUT_18") (pintype "output"))
      (node (ref "IC16") (pin "19") (pinfunction "OUT_19") (pintype "output"))
      (node (ref "IC16") (pin "20") (pinfunction "OUT_20") (pintype "output"))
      (node (ref "R101") (pin "2") (pinfunction "2_2") (pintype "passive"))
    )
    (net (code "37") (name "P1V4") (class "Default")
      (node (ref "C80") (pin "2") (pinfunction "2_2") (pintype "passive"))
      (node (ref "C81") (pin "1") (pinfunction "1_1") (pintype "passive"))
      (node (ref "L12") (pin "1") (pinfunction "1_1") (pintype "passive"))
      (node (ref "L6") (pin "2") (pinfunction "2_2") (pintype "passive"))
    )
    (net (code "38") (name "P1V8") (class "Default")
      (node (ref "C84") (pin "2") (pinfunction "2_2") (pintype "passive"))
      (node (ref "IC11") (pin "1") (pinfunction "OUT_1") (pintype "power_in"))
      (node (ref "IC11") (pin "18") (pinfunction "OUT_18") (pintype "power_in"))
      (node (ref "IC11") (pin "19") (pinfunction "OUT_19") (pintype "power_in"))
      (node (ref "IC11") (pin "20") (pinfunction "OUT_20") (pintype "power_in"))
      (node (ref "L7") (pin "1") (pinfunction "1_1") (pintype "passive"))
      (node (ref "L8") (pin "1") (pinfunction "1_1") (pintype "passive"))
      (node (ref "R90") (pin "2") (pinfunction "2_2") (pintype "passive"))
    )
    (net (code "39") (name "P1V8A") (class "Default")
      (node (ref "L7") (pin "2") (pinfunction "2_2") (pintype "passive"))
    )
    (net (code "40") (name "P1V8D") (class "Default")
      (node (ref "L8") (pin "2") (pinfunction "2_2") (pintype "passive"))
    )
    (net (code "41") (name "P1V9A") (class "Default")
      (node (ref "C101") (pin "2") (pinfunction "2_2") (pintype "passive"))
      (node (ref "C77") (pin "2") (pinfunction "2_2") (pintype "passive"))
      (node (ref "IC12") (pin "1") (pinfunction "OUT_1") (pintype "power_in"))
      (node (ref "IC12") (pin "18") (pinfunction "OUT_18") (pintype "power_in"))
      (node (ref "IC12") (pin "19") (pinfunction "OUT_19") (pintype "power_in"))
      (node (ref "IC12") (pin "20") (pinfunction "OUT_20") (pintype "power_in"))
      (node (ref "IC9") (pin "1") (pinfunction "OUT_1") (pintype "power_in"))
      (node (ref "IC9") (pin "18") (pinfunction "OUT_18") (pintype "power_in"))
      (node (ref "IC9") (pin "19") (pinfunction "OUT_19") (pintype "power_in"))
      (node (ref "IC9") (pin "20") (pinfunction "OUT_20") (pintype "power_in"))
      (node (ref "R88") (pin "2") (pinfunction "2_2") (pintype "passive"))
      (node (ref "R92") (pin "2") (pinfunction "2_2") (pintype "passive"))
    )
    (net (code "42") (name "P2V0") (class "Default")
      (node (ref "C78") (pin "1") (pinfunction "1_1") (pintype "passive"))
      (node (ref "C96") (pin "2") (pinfunction "2_2") (pintype "passive"))
      (node (ref "C97") (pin "1") (pinfunction "1_1") (pintype "passive"))
      (node (ref "IC11") (pin "5") (pinfunction "IN_5") (pintype "input"))
      (node (ref "IC11") (pin "6") (pinfunction "IN_6") (pintype "input"))
      (node (ref "IC11") (pin "7") (pinfunction "IN_7") (pintype "input"))
      (node (ref "IC11") (pin "8") (pinfunction "IN_8") (pintype "input"))
      (node (ref "L9") (pin "2") (pinfunction "2_2") (pintype "passive"))
    )
    (net (code "43") (name "P2V1") (class "Default")
      (node (ref "C87") (pin "2") (pinfunction "2_2") (pintype "passive"))
      (node (ref "C88") (pin "1") (pinfunction "1_1") (pintype "passive"))
      (node (ref "L1") (pin "1") (pinfunction "1_1") (pintype "passive"))
      (node (ref "L2") (pin "1") (pinfunction "1_1") (pintype "passive"))
      (node (ref "L3") (pin "2") (pinfunction "2_2") (pintype "passive"))
    )
    (net (code "44") (name "P2V5A") (class "Default")
      (node (ref "C108") (pin "2") (pinfunction "2_2") (pintype "passive"))
      (node (ref "IC15") (pin "1") (pinfunction "OUT_1") (pintype "output"))
      (node (ref "IC15") (pin "18") (pinfunction "OUT_18") (pintype "output"))
      (node (ref "IC15") (pin "19") (pinfunction "OUT_19") (pintype "output"))
      (node (ref "IC15") (pin "20") (pinfunction "OUT_20") (pintype "output"))
      (node (ref "R100") (pin "2") (pinfunction "2_2") (pintype "passive"))
    )
    (net (code "45") (name "P3V3") (class "Default")
      (node (ref "L10") (pin "1") (pinfunction "1_1") (pintype "passive"))
      (node (ref "L11") (pin "1") (pinfunction "1_1") (pintype "passive"))
      (node (ref "LD2") (pin "2") (pinfunction "A_2") (pintype "passive"))
      (node (ref "R138") (pin "1") (pinfunction "1_1") (pintype "passive"))
    )
    (net (code "46") (name "P3V15A") (class "Default")
      (node (ref "C93") (pin "2") (pinfunction "2_2") (pintype "passive"))
      (node (ref "IC14") (pin "1") (pinfunction "OUT_1") (pintype "output"))
      (node (ref "IC14") (pin "18") (pinfunction "OUT_18") (pintype "output"))
      (node (ref "IC14") (pin "19") (pinfunction "OUT_19") (pintype "output"))
      (node (ref "IC14") (pin "20") (pinfunction "OUT_20") (pintype "output"))
      (node (ref "R95") (pin "2") (pinfunction "2_2") (pintype "passive"))
    )
    (net (code "47") (name "P5V0A") (class "Default")
      (node (ref "C106") (pin "2") (pinfunction "2_2") (pintype "passive"))
      (node (ref "C107") (pin "2") (pinfunction "2_2") (pintype "passive"))
      (node (ref "C76") (pin "2") (pinfunction "2_2") (pintype "passive"))
      (node (ref "C83") (pin "2") (pinfunction "2_2") (pintype "passive"))
      (node (ref "C92") (pin "2") (pinfunction "2_2") (pintype "passive"))
      (node (ref "C98") (pin "2") (pinfunction "2_2") (pintype "passive"))
      (node (ref "IC11") (pin "10") (pinfunction "BIAS_10") (pintype "input"))
      (node (ref "IC11") (pin "11") (pinfunction "EN_11") (pintype "input"))
      (node (ref "IC12") (pin "10") (pinfunction "BIAS_10") (pintype "input"))
      (node (ref "IC12") (pin "11") (pinfunction "EN_11") (pintype "input"))
      (node (ref "IC14") (pin "10") (pinfunction "BIAS_10") (pintype "input"))
      (node (ref "IC14") (pin "11") (pinfunction "EN_11") (pintype "input"))
      (node (ref "IC15") (pin "10") (pinfunction "BIAS_10") (pintype "input"))
      (node (ref "IC15") (pin "11") (pinfunction "EN_11") (pintype "input"))
      (node (ref "IC16") (pin "10") (pinfunction "BIAS_10") (pintype "input"))
      (node (ref "IC16") (pin "11") (pinfunction "EN_11") (pintype "input"))
      (node (ref "IC9") (pin "10") (pinfunction "BIAS_10") (pintype "input"))
      (node (ref "IC9") (pin "11") (pinfunction "EN_11") (pintype "input"))
    )
    (net (code "48") (name "P12V0") (class "Default")
      (node (ref "C100") (pin "2") (pinfunction "2_2") (pintype "passive"))
      (node (ref "C90") (pin "2") (pinfunction "2_2") (pintype "passive"))
      (node (ref "C91") (pin "2") (pinfunction "2_2") (pintype "passive"))
      (node (ref "C99") (pin "2") (pinfunction "2_2") (pintype "passive"))
      (node (ref "IC10") (pin "A2") (pinfunction "VIN1_A2") (pintype "power_in"))
      (node (ref "IC10") (pin "B3") (pinfunction "VIN1_B3") (pintype "power_in"))
      (node (ref "IC10") (pin "D3") (pinfunction "VIN2_D3") (pintype "power_in"))
      (node (ref "IC10") (pin "E2") (pinfunction "VIN2_E2") (pintype "power_in"))
      (node (ref "IC13") (pin "A2") (pinfunction "VIN1_A2") (pintype "power_in"))
      (node (ref "IC13") (pin "B3") (pinfunction "VIN1_B3") (pintype "power_in"))
      (node (ref "IC13") (pin "D3") (pinfunction "VIN2_D3") (pintype "power_in"))
      (node (ref "IC13") (pin "E2") (pinfunction "VIN2_E2") (pintype "power_in"))
    )
    (net (code "49") (name "VADJ") (class "Default")
      (node (ref "R105") (pin "2") (pinfunction "2_2") (pintype "passive"))
      (node (ref "T3") (pin "5") (pinfunction "G1_5") (pintype "passive"))
    )
    (net (code "51") (name "unconnected-(IC9-NC-Pad2)") (class "Default")
      (node (ref "IC9") (pin "2") (pinfunction "NC_2") (pintype "passive+no_connect"))
    )
    (net (code "52") (name "unconnected-(IC9-NC-Pad3)") (class "Default")
      (node (ref "IC9") (pin "3") (pinfunction "NC_3") (pintype "passive+no_connect"))
    )
    (net (code "53") (name "unconnected-(IC9-NC-Pad4)") (class "Default")
      (node (ref "IC9") (pin "4") (pinfunction "NC_4") (pintype "passive+no_connect"))
    )
    (net (code "54") (name "unconnected-(IC9-NC-Pad13)") (class "Default")
      (node (ref "IC9") (pin "13") (pinfunction "NC_13") (pintype "passive+no_connect"))
    )
    (net (code "55") (name "unconnected-(IC9-NC-Pad14)") (class "Default")
      (node (ref "IC9") (pin "14") (pinfunction "NC_14") (pintype "passive+no_connect"))
    )
    (net (code "56") (name "unconnected-(IC9-NC-Pad17)") (class "Default")
      (node (ref "IC9") (pin "17") (pinfunction "NC_17") (pintype "passive+no_connect"))
    )
    (net (code "57") (name "unconnected-(IC9-SS-Pad15)") (class "Default")
      (node (ref "IC9") (pin "15") (pinfunction "SS_15") (pintype "output+no_connect"))
    )
    (net (code "58") (name "unconnected-(IC11-NC-Pad2)") (class "Default")
      (node (ref "IC11") (pin "2") (pinfunction "NC_2") (pintype "passive+no_connect"))
    )
    (net (code "59") (name "unconnected-(IC11-NC-Pad3)") (class "Default")
      (node (ref "IC11") (pin "3") (pinfunction "NC_3") (pintype "passive+no_connect"))
    )
    (net (code "60") (name "unconnected-(IC11-NC-Pad4)") (class "Default")
      (node (ref "IC11") (pin "4") (pinfunction "NC_4") (pintype "passive+no_connect"))
    )
    (net (code "61") (name "unconnected-(IC11-NC-Pad13)") (class "Default")
      (node (ref "IC11") (pin "13") (pinfunction "NC_13") (pintype "passive+no_connect"))
    )
    (net (code "62") (name "unconnected-(IC11-NC-Pad14)") (class "Default")
      (node (ref "IC11") (pin "14") (pinfunction "NC_14") (pintype "passive+no_connect"))
    )
    (net (code "63") (name "unconnected-(IC11-NC-Pad17)") (class "Default")
      (node (ref "IC11") (pin "17") (pinfunction "NC_17") (pintype "passive+no_connect"))
    )
    (net (code "64") (name "unconnected-(IC11-SS-Pad15)") (class "Default")
      (node (ref "IC11") (pin "15") (pinfunction "SS_15") (pintype "output+no_connect"))
    )
    (net (code "65") (name "unconnected-(IC12-NC-Pad2)") (class "Default")
      (node (ref "IC12") (pin "2") (pinfunction "NC_2") (pintype "passive+no_connect"))
    )
    (net (code "66") (name "unconnected-(IC12-NC-Pad3)") (class "Default")
      (node (ref "IC12") (pin "3") (pinfunction "NC_3") (pintype "passive+no_connect"))
    )
    (net (code "67") (name "unconnected-(IC12-NC-Pad4)") (class "Default")
      (node (ref "IC12") (pin "4") (pinfunction "NC_4") (pintype "passive+no_connect"))
    )
    (net (code "68") (name "unconnected-(IC12-NC-Pad13)") (class "Default")
      (node (ref "IC12") (pin "13") (pinfunction "NC_13") (pintype "passive+no_connect"))
    )
    (net (code "69") (name "unconnected-(IC12-NC-Pad14)") (class "Default")
      (node (ref "IC12") (pin "14") (pinfunction "NC_14") (pintype "passive+no_connect"))
    )
    (net (code "70") (name "unconnected-(IC12-NC-Pad17)") (class "Default")
      (node (ref "IC12") (pin "17") (pinfunction "NC_17") (pintype "passive+no_connect"))
    )
    (net (code "71") (name "unconnected-(IC12-SS-Pad15)") (class "Default")
      (node (ref "IC12") (pin "15") (pinfunction "SS_15") (pintype "output+no_connect"))
    )
    (net (code "72") (name "unconnected-(IC14-NC-Pad2)") (class "Default")
      (node (ref "IC14") (pin "2") (pinfunction "NC_2") (pintype "passive+no_connect"))
    )
    (net (code "73") (name "unconnected-(IC14-NC-Pad3)") (class "Default")
      (node (ref "IC14") (pin "3") (pinfunction "NC_3") (pintype "passive+no_connect"))
    )
    (net (code "74") (name "unconnected-(IC14-NC-Pad4)") (class "Default")
      (node (ref "IC14") (pin "4") (pinfunction "NC_4") (pintype "passive+no_connect"))
    )
    (net (code "75") (name "unconnected-(IC14-NC-Pad13)") (class "Default")
      (node (ref "IC14") (pin "13") (pinfunction "NC_13") (pintype "passive+no_connect"))
    )
    (net (code "76") (name "unconnected-(IC14-NC-Pad14)") (class "Default")
      (node (ref "IC14") (pin "14") (pinfunction "NC_14") (pintype "passive+no_connect"))
    )
    (net (code "77") (name "unconnected-(IC14-NC-Pad17)") (class "Default")
      (node (ref "IC14") (pin "17") (pinfunction "NC_17") (pintype "passive+no_connect"))
    )
    (net (code "78") (name "unconnected-(IC14-SS-Pad15)") (class "Default")
      (node (ref "IC14") (pin "15") (pinfunction "SS_15") (pintype "input+no_connect"))
    )
    (net (code "79") (name "unconnected-(IC15-NC-Pad2)") (class "Default")
      (node (ref "IC15") (pin "2") (pinfunction "NC_2") (pintype "passive+no_connect"))
    )
    (net (code "80") (name "unconnected-(IC15-NC-Pad3)") (class "Default")
      (node (ref "IC15") (pin "3") (pinfunction "NC_3") (pintype "passive+no_connect"))
    )
    (net (code "81") (name "unconnected-(IC15-NC-Pad4)") (class "Default")
      (node (ref "IC15") (pin "4") (pinfunction "NC_4") (pintype "passive+no_connect"))
    )
    (net (code "82") (name "unconnected-(IC15-NC-Pad13)") (class "Default")
      (node (ref "IC15") (pin "13") (pinfunction "NC_13") (pintype "passive+no_connect"))
    )
    (net (code "83") (name "unconnected-(IC15-NC-Pad14)") (class "Default")
      (node (ref "IC15") (pin "14") (pinfunction "NC_14") (pintype "passive+no_connect"))
    )
    (net (code "84") (name "unconnected-(IC15-NC-Pad17)") (class "Default")
      (node (ref "IC15") (pin "17") (pinfunction "NC_17") (pintype "passive+no_connect"))
    )
    (net (code "85") (name "unconnected-(IC15-SS-Pad15)") (class "Default")
      (node (ref "IC15") (pin "15") (pinfunction "SS_15") (pintype "input+no_connect"))
    )
    (net (code "86") (name "unconnected-(IC16-NC-Pad2)") (class "Default")
      (node (ref "IC16") (pin "2") (pinfunction "NC_2") (pintype "passive+no_connect"))
    )
    (net (code "87") (name "unconnected-(IC16-NC-Pad3)") (class "Default")
      (node (ref "IC16") (pin "3") (pinfunction "NC_3") (pintype "passive+no_connect"))
    )
    (net (code "88") (name "unconnected-(IC16-NC-Pad4)") (class "Default")
      (node (ref "IC16") (pin "4") (pinfunction "NC_4") (pintype "passive+no_connect"))
    )
    (net (code "89") (name "unconnected-(IC16-NC-Pad13)") (class "Default")
      (node (ref "IC16") (pin "13") (pinfunction "NC_13") (pintype "passive+no_connect"))
    )
    (net (code "90") (name "unconnected-(IC16-NC-Pad14)") (class "Default")
      (node (ref "IC16") (pin "14") (pinfunction "NC_14") (pintype "passive+no_connect"))
    )
    (net (code "91") (name "unconnected-(IC16-NC-Pad17)") (class "Default")
      (node (ref "IC16") (pin "17") (pinfunction "NC_17") (pintype "passive+no_connect"))
    )
    (net (code "92") (name "unconnected-(IC16-SS-Pad15)") (class "Default")
      (node (ref "IC16") (pin "15") (pinfunction "SS_15") (pintype "input+no_connect"))
    )
    (net (code "93") (name "unconnected-(R89-Pad2)") (class "Default")
      (node (ref "R89") (pin "2") (pinfunction "2_2") (pintype "passive"))
    )
    (net (code "94") (name "unconnected-(R94-Pad2)") (class "Default")
      (node (ref "R94") (pin "2") (pinfunction "2_2") (pintype "passive"))
    )
    (net (code "95") (name "unconnected-(R96-Pad2)") (class "Default")
      (node (ref "R96") (pin "2") (pinfunction "2_2") (pintype "passive"))
    )
  )
)
